# CH340G.net
KiCad netlist of a schematic drawn in Altium Designer
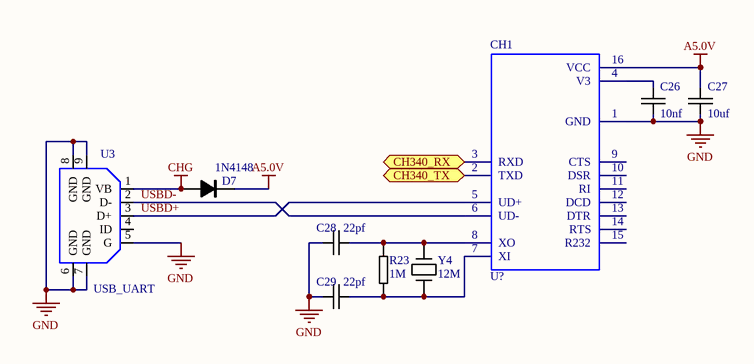
[diagram p0: CH340G.SchDoc]

(export (version "E")
  (design (tool "Eeschema 10.0.6"))
  (components
    (comp (ref "C26")
      (value "10nf")
      (footprint "0603")
      (description "贴片")
      (libsource (lib "authuir") (part "CAP_Chip"))
    )
    (comp (ref "C27")
      (value "10uf")
      (footprint "0603")
      (description "贴片")
      (libsource (lib "authuir") (part "CAP_Chip"))
    )
    (comp (ref "C28")
      (value "22pf")
      (footprint "0603")
      (description "贴片")
      (libsource (lib "authuir") (part "CAP_Chip"))
    )
    (comp (ref "C29")
      (value "22pf")
      (footprint "0603")
      (description "贴片")
      (libsource (lib "authuir") (part "CAP_Chip"))
    )
    (comp (ref "CH1")
      (value "U?")
      (footprint "SOP-16(230)")
      (description "USB-TTL芯片")
      (libsource (lib "SIT器件") (part "CH340G"))
    )
    (comp (ref "D7")
      (value "1N4148")
      (footprint "DO-35")
      (description "1.04.08.0001")
      (libsource (lib "晶体管") (part "1N4148(DO-35)"))
    )
    (comp (ref "R23")
      (value "1M")
      (footprint "0603")
      (description "贴片")
      (libsource (lib "authuir") (part "RES_Chip"))
    )
    (comp (ref "U3")
      (value "USB_UART")
      (footprint "USB_Mini_B")
      (libsource (lib "authuir") (part "USB_Mini_B"))
    )
    (comp (ref "Y4")
      (value "12M")
      (footprint "XTAL(HC-49)")
      (description "1.07.02.0011")
      (libsource (lib "振荡器") (part "XTAL(12.000M,HC-49US)"))
    )
  )
  (nets
    (net (code "1") (name "/CH340_RX") (class "Default")
      (node (ref "CH1") (pin "3") (pinfunction "RXD_3") (pintype "passive"))
    )
    (net (code "2") (name "/CH340_TX") (class "Default")
      (node (ref "CH1") (pin "2") (pinfunction "TXD_2") (pintype "passive"))
    )
    (net (code "3") (name "/USBD+") (class "Default")
      (node (ref "CH1") (pin "5") (pinfunction "UD+_5") (pintype "passive"))
      (node (ref "U3") (pin "3") (pinfunction "D+_3") (pintype "passive"))
    )
    (net (code "4") (name "/USBD-") (class "Default")
      (node (ref "CH1") (pin "6") (pinfunction "UD-_6") (pintype "passive"))
      (node (ref "U3") (pin "2") (pinfunction "D-_2") (pintype "passive"))
    )
    (net (code "5") (name "A5.0V") (class "Default")
      (node (ref "C27") (pin "1") (pinfunction "1_1") (pintype "passive"))
      (node (ref "CH1") (pin "16") (pinfunction "VCC_16") (pintype "passive"))
      (node (ref "D7") (pin "2") (pinfunction "K_2") (pintype "passive"))
    )
    (net (code "6") (name "CHG") (class "Default")
      (node (ref "D7") (pin "1") (pinfunction "A_1") (pintype "passive"))
      (node (ref "U3") (pin "1") (pinfunction "VB_1") (pintype "passive"))
    )
    (net (code "7") (name "GND") (class "Default")
      (node (ref "C26") (pin "2") (pinfunction "2_2") (pintype "passive"))
      (node (ref "C27") (pin "2") (pinfunction "2_2") (pintype "passive"))
      (node (ref "C28") (pin "1") (pinfunction "1_1") (pintype "passive"))
      (node (ref "C29") (pin "1") (pinfunction "1_1") (pintype "passive"))
      (node (ref "CH1") (pin "1") (pinfunction "GND_1") (pintype "passive"))
      (node (ref "U3") (pin "5") (pinfunction "G_5") (pintype "passive"))
      (node (ref "U3") (pin "6") (pinfunction "GND_6") (pintype "passive"))
      (node (ref "U3") (pin "7") (pinfunction "GND_7") (pintype "passive"))
      (node (ref "U3") (pin "8") (pinfunction "GND_8") (pintype "passive"))
      (node (ref "U3") (pin "9") (pinfunction "GND_9") (pintype "passive"))
    )
    (net (code "8") (name "Net-(CH1-V3)") (class "Default")
      (node (ref "C26") (pin "1") (pinfunction "1_1") (pintype "passive"))
      (node (ref "CH1") (pin "4") (pinfunction "V3_4") (pintype "passive"))
    )
    (net (code "9") (name "Net-(CH1-XI)") (class "Default")
      (node (ref "C29") (pin "2") (pinfunction "2_2") (pintype "passive"))
      (node (ref "CH1") (pin "7") (pinfunction "XI_7") (pintype "passive"))
      (node (ref "R23") (pin "2") (pinfunction "2_2") (pintype "passive"))
      (node (ref "Y4") (pin "2") (pinfunction "2_2") (pintype "passive"))
    )
    (net (code "10") (name "Net-(CH1-XO)") (class "Default")
      (node (ref "C28") (pin "2") (pinfunction "2_2") (pintype "passive"))
      (node (ref "CH1") (pin "8") (pinfunction "XO_8") (pintype "passive"))
      (node (ref "R23") (pin "1") (pinfunction "1_1") (pintype "passive"))
      (node (ref "Y4") (pin "1") (pinfunction "1_1") (pintype "passive"))
    )
    (net (code "11") (name "unconnected-(CH1-CTS-Pad9)") (class "Default")
      (node (ref "CH1") (pin "9") (pinfunction "CTS_9") (pintype "passive"))
    )
    (net (code "12") (name "unconnected-(CH1-DCD-Pad12)") (class "Default")
      (node (ref "CH1") (pin "12") (pinfunction "DCD_12") (pintype "passive"))
    )
    (net (code "13") (name "unconnected-(CH1-DSR-Pad10)") (class "Default")
      (node (ref "CH1") (pin "10") (pinfunction "DSR_10") (pintype "passive"))
    )
    (net (code "14") (name "unconnected-(CH1-DTR-Pad13)") (class "Default")
      (node (ref "CH1") (pin "13") (pinfunction "DTR_13") (pintype "passive"))
    )
    (net (code "15") (name "unconnected-(CH1-R232-Pad15)") (class "Default")
      (node (ref "CH1") (pin "15") (pinfunction "R232_15") (pintype "passive"))
    )
    (net (code "16") (name "unconnected-(CH1-RI-Pad11)") (class "Default")
      (node (ref "CH1") (pin "11") (pinfunction "RI_11") (pintype "passive"))
    )
    (net (code "17") (name "unconnected-(CH1-RTS-Pad14)") (class "Default")
      (node (ref "CH1") (pin "14") (pinfunction "RTS_14") (pintype "passive"))
    )
    (net (code "18") (name "unconnected-(U3-ID-Pad4)") (class "Default")
      (node (ref "U3") (pin "4") (pinfunction "ID_4") (pintype "passive"))
    )
  )
)
